# DobbelSteen_no_programing_header.net
KiCad netlist of a schematic drawn in EAGLE
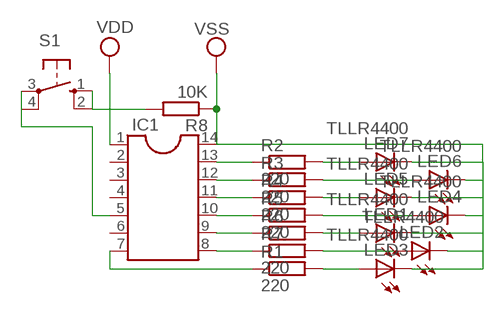
[diagram p0: schematic, sheet 1]

(export (version "E")
  (design (tool "Eeschema 10.0.6"))
  (components
    (comp (ref "IC1")
      (value "DIL14S")
      (footprint "eagle-import:SOCKET-14")
      (libsource (lib "eagle-import") (part "DIL14S"))
    )
    (comp (ref "LED1")
      (value "TLLR4400")
      (footprint "eagle-import:LED3MM")
      (fields (field (name "MF") "VISHAY SEMICONDUCTOR"))
      (libsource (lib "eagle-import") (part "TLLR4400"))
    )
    (comp (ref "LED2")
      (value "TLLR4400")
      (footprint "eagle-import:LED3MM")
      (fields (field (name "MF") "VISHAY SEMICONDUCTOR"))
      (libsource (lib "eagle-import") (part "TLLR4400"))
    )
    (comp (ref "LED3")
      (value "TLLR4400")
      (footprint "eagle-import:LED3MM")
      (fields (field (name "MF") "VISHAY SEMICONDUCTOR"))
      (libsource (lib "eagle-import") (part "TLLR4400"))
    )
    (comp (ref "LED4")
      (value "TLLR4400")
      (footprint "eagle-import:LED3MM")
      (fields (field (name "MF") "VISHAY SEMICONDUCTOR"))
      (libsource (lib "eagle-import") (part "TLLR4400"))
    )
    (comp (ref "LED5")
      (value "TLLR4400")
      (footprint "eagle-import:LED3MM")
      (fields (field (name "MF") "VISHAY SEMICONDUCTOR"))
      (libsource (lib "eagle-import") (part "TLLR4400"))
    )
    (comp (ref "LED6")
      (value "TLLR4400")
      (footprint "eagle-import:LED3MM")
      (fields (field (name "MF") "VISHAY SEMICONDUCTOR"))
      (libsource (lib "eagle-import") (part "TLLR4400"))
    )
    (comp (ref "LED7")
      (value "TLLR4400")
      (footprint "eagle-import:LED3MM")
      (fields (field (name "MF") "VISHAY SEMICONDUCTOR"))
      (libsource (lib "eagle-import") (part "TLLR4400"))
    )
    (comp (ref "R1")
      (value "220")
      (footprint "eagle-import:0204_7")
      (libsource (lib "eagle-import") (part "R0204/7"))
    )
    (comp (ref "R2")
      (value "220")
      (footprint "eagle-import:0204_7")
      (libsource (lib "eagle-import") (part "R0204/7"))
    )
    (comp (ref "R3")
      (value "220")
      (footprint "eagle-import:0204_7")
      (libsource (lib "eagle-import") (part "R0204/7"))
    )
    (comp (ref "R4")
      (value "220")
      (footprint "eagle-import:0204_7")
      (libsource (lib "eagle-import") (part "R0204/7"))
    )
    (comp (ref "R5")
      (value "220")
      (footprint "eagle-import:0204_7")
      (libsource (lib "eagle-import") (part "R0204/7"))
    )
    (comp (ref "R6")
      (value "R0204/7")
      (footprint "eagle-import:0204_7")
      (libsource (lib "eagle-import") (part "R0204/7"))
    )
    (comp (ref "R7")
      (value "220")
      (footprint "eagle-import:0204_7")
      (libsource (lib "eagle-import") (part "R0204/7"))
    )
    (comp (ref "R8")
      (value "10K")
      (footprint "eagle-import:0204_7")
      (libsource (lib "eagle-import") (part "R0204/7"))
    )
    (comp (ref "S1")
      (value "10-XX")
      (footprint "eagle-import:B3F-10XX")
      (fields (field (name "MPN") "B3F-1000"))
      (libsource (lib "eagle-import") (part "10-XX"))
    )
  )
  (nets
    (net (code "1") (name "Net-(IC1-Pad7)") (class "Default")
      (node (ref "IC1") (pin "7") (pinfunction "7_7") (pintype "passive"))
      (node (ref "R1") (pin "1") (pinfunction "1_1") (pintype "passive"))
    )
    (net (code "2") (name "Net-(IC1-Pad8)") (class "Default")
      (node (ref "IC1") (pin "8") (pinfunction "8_8") (pintype "passive"))
      (node (ref "R7") (pin "1") (pinfunction "1_1") (pintype "passive"))
    )
    (net (code "3") (name "Net-(IC1-Pad9)") (class "Default")
      (node (ref "IC1") (pin "9") (pinfunction "9_9") (pintype "passive"))
      (node (ref "R6") (pin "1") (pinfunction "1_1") (pintype "passive"))
    )
    (net (code "4") (name "Net-(IC1-Pad10)") (class "Default")
      (node (ref "IC1") (pin "10") (pinfunction "10_10") (pintype "passive"))
      (node (ref "R5") (pin "1") (pinfunction "1_1") (pintype "passive"))
    )
    (net (code "5") (name "Net-(IC1-Pad11)") (class "Default")
      (node (ref "IC1") (pin "11") (pinfunction "11_11") (pintype "passive"))
      (node (ref "R4") (pin "1") (pinfunction "1_1") (pintype "passive"))
    )
    (net (code "6") (name "Net-(IC1-Pad12)") (class "Default")
      (node (ref "IC1") (pin "12") (pinfunction "12_12") (pintype "passive"))
      (node (ref "R3") (pin "1") (pinfunction "1_1") (pintype "passive"))
    )
    (net (code "7") (name "Net-(IC1-Pad13)") (class "Default")
      (node (ref "IC1") (pin "13") (pinfunction "13_13") (pintype "passive"))
      (node (ref "R2") (pin "1") (pinfunction "1_1") (pintype "passive"))
    )
    (net (code "8") (name "Net-(LED1-PadA)") (class "Default")
      (node (ref "LED1") (pin "A") (pinfunction "A_A") (pintype "passive"))
      (node (ref "R6") (pin "2") (pinfunction "2_2") (pintype "passive"))
    )
    (net (code "9") (name "Net-(LED2-PadA)") (class "Default")
      (node (ref "LED2") (pin "A") (pinfunction "A_A") (pintype "passive"))
      (node (ref "R7") (pin "2") (pinfunction "2_2") (pintype "passive"))
    )
    (net (code "10") (name "Net-(LED3-PadA)") (class "Default")
      (node (ref "LED3") (pin "A") (pinfunction "A_A") (pintype "passive"))
      (node (ref "R1") (pin "2") (pinfunction "2_2") (pintype "passive"))
    )
    (net (code "11") (name "Net-(LED4-PadA)") (class "Default")
      (node (ref "LED4") (pin "A") (pinfunction "A_A") (pintype "passive"))
      (node (ref "R5") (pin "2") (pinfunction "2_2") (pintype "passive"))
    )
    (net (code "12") (name "Net-(LED5-PadA)") (class "Default")
      (node (ref "LED5") (pin "A") (pinfunction "A_A") (pintype "passive"))
      (node (ref "R4") (pin "2") (pinfunction "2_2") (pintype "passive"))
    )
    (net (code "13") (name "Net-(LED6-PadA)") (class "Default")
      (node (ref "LED6") (pin "A") (pinfunction "A_A") (pintype "passive"))
      (node (ref "R3") (pin "2") (pinfunction "2_2") (pintype "passive"))
    )
    (net (code "14") (name "Net-(LED7-PadA)") (class "Default")
      (node (ref "LED7") (pin "A") (pinfunction "A_A") (pintype "passive"))
      (node (ref "R2") (pin "2") (pinfunction "2_2") (pintype "passive"))
    )
    (net (code "15") (name "Net-(S1-P)") (class "Default")
      (node (ref "IC1") (pin "5") (pinfunction "5_5") (pintype "passive"))
      (node (ref "S1") (pin "3") (pinfunction "P_3") (pintype "passive"))
      (node (ref "S1") (pin "4") (pinfunction "P1_4") (pintype "passive"))
    )
    (net (code "16") (name "Net-(S1-S)") (class "Default")
      (node (ref "R8") (pin "2") (pinfunction "2_2") (pintype "passive"))
      (node (ref "S1") (pin "1") (pinfunction "S_1") (pintype "passive"))
      (node (ref "S1") (pin "2") (pinfunction "S1_2") (pintype "passive"))
    )
    (net (code "17") (name "VDD") (class "Default")
      (node (ref "IC1") (pin "1") (pinfunction "1_1") (pintype "passive"))
    )
    (net (code "18") (name "VSS") (class "Default")
      (node (ref "IC1") (pin "14") (pinfunction "14_14") (pintype "passive"))
      (node (ref "LED1") (pin "K") (pinfunction "C_K") (pintype "passive"))
      (node (ref "LED2") (pin "K") (pinfunction "C_K") (pintype "passive"))
      (node (ref "LED3") (pin "K") (pinfunction "C_K") (pintype "passive"))
      (node (ref "LED4") (pin "K") (pinfunction "C_K") (pintype "passive"))
      (node (ref "LED5") (pin "K") (pinfunction "C_K") (pintype "passive"))
      (node (ref "LED6") (pin "K") (pinfunction "C_K") (pintype "passive"))
      (node (ref "LED7") (pin "K") (pinfunction "C_K") (pintype "passive"))
      (node (ref "R8") (pin "1") (pinfunction "1_1") (pintype "passive"))
    )
    (net (code "19") (name "unconnected-(IC1-Pad2)") (class "Default")
      (node (ref "IC1") (pin "2") (pinfunction "2_2") (pintype "passive"))
    )
    (net (code "20") (name "unconnected-(IC1-Pad3)") (class "Default")
      (node (ref "IC1") (pin "3") (pinfunction "3_3") (pintype "passive"))
    )
    (net (code "21") (name "unconnected-(IC1-Pad4)") (class "Default")
      (node (ref "IC1") (pin "4") (pinfunction "4_4") (pintype "passive"))
    )
    (net (code "22") (name "unconnected-(IC1-Pad6)") (class "Default")
      (node (ref "IC1") (pin "6") (pinfunction "6_6") (pintype "passive"))
    )
  )
)
